# EqualizerTop.net
KiCad netlist of a schematic drawn in Altium Designer
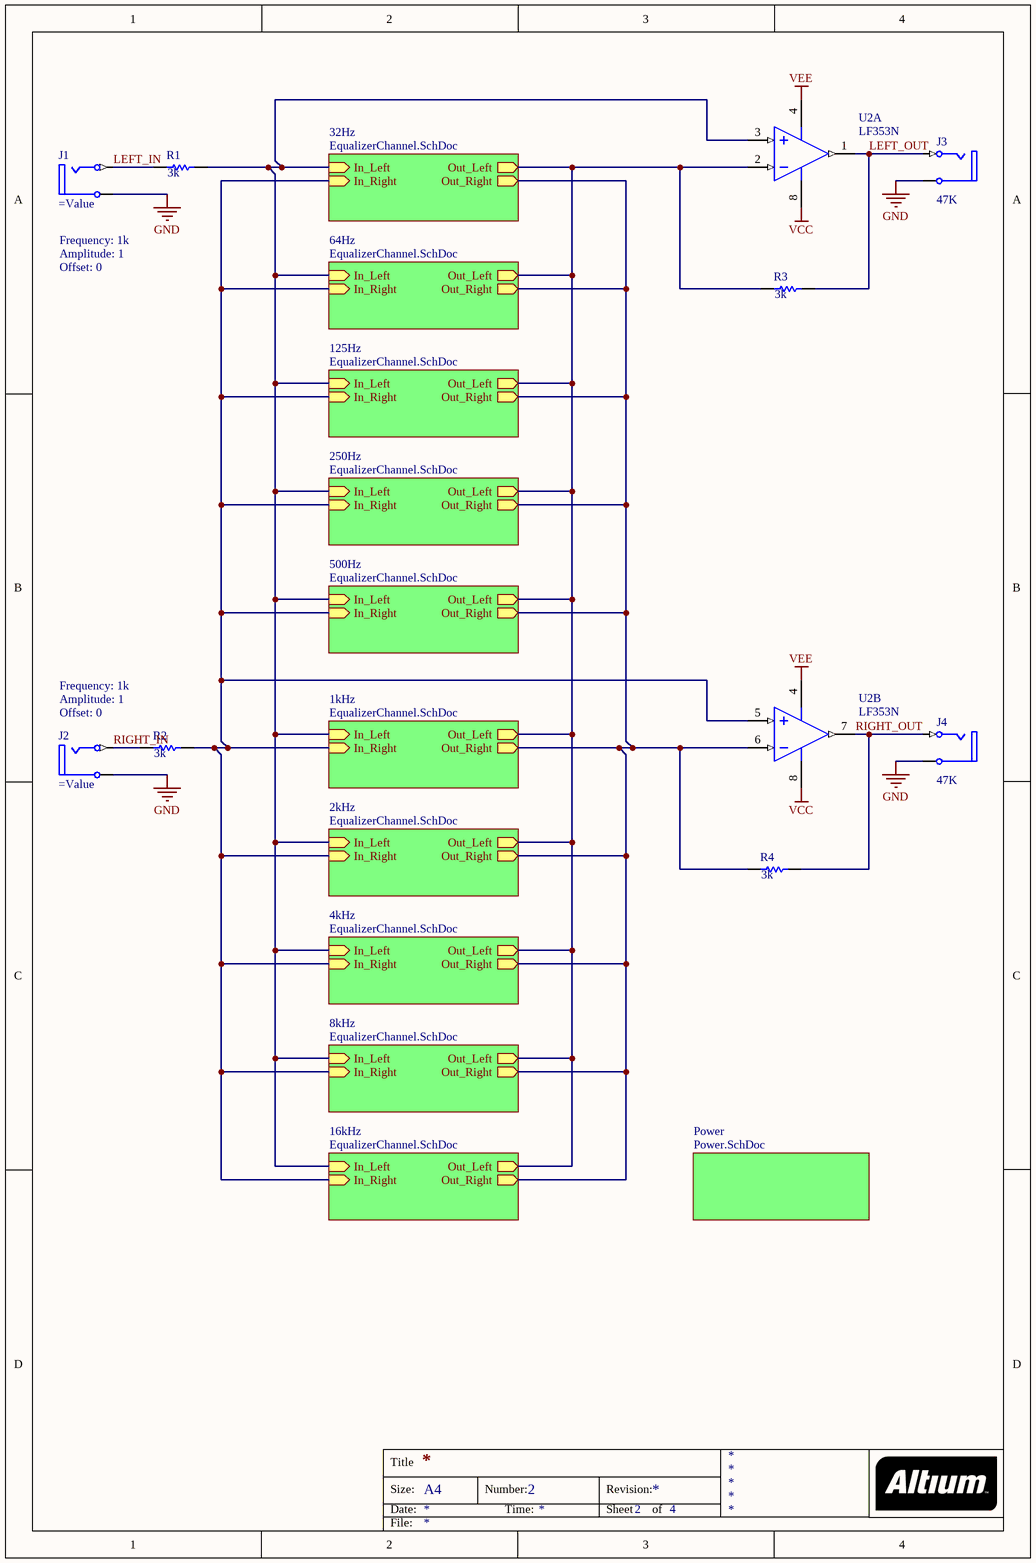
[diagram p0: EqualizerTop.SchDoc]

(export (version "E")
  (design (tool "Eeschema 10.0.6"))
  (components
    (comp (ref "J1")
      (value "~")
      (footprint "AudioEqualizer:RCA/4.5-H2")
      (description "RCA Phono Jack, Right Angle, Thru-Hole, Snap-In")
      (fields
        (field (name "OFFSET") "0")
        (field (name "AMPLITUDE") "1")
        (field (name "FREQUENCY") "1k")
        (field (name "PUBLISHER") "Altium Limited")
      )
      (libsource (lib "Miscellaneous Connectors") (part "RCA"))
    )
    (comp (ref "J2")
      (value "~")
      (footprint "AudioEqualizer:RCA/4.5-H2")
      (description "RCA Phono Jack, Right Angle, Thru-Hole, Snap-In")
      (fields
        (field (name "OFFSET") "0")
        (field (name "AMPLITUDE") "1")
        (field (name "FREQUENCY") "1k")
        (field (name "PUBLISHER") "Altium Limited")
      )
      (libsource (lib "Miscellaneous Connectors") (part "RCA"))
    )
    (comp (ref "J3")
      (value "47K")
      (footprint "AudioEqualizer:RCA/4.5-H2")
      (description "RCA Phono Jack, Right Angle, Thru-Hole, Snap-In")
      (fields (field (name "PUBLISHER") "Altium Limited"))
      (libsource (lib "Miscellaneous Connectors") (part "RCA"))
    )
    (comp (ref "J4")
      (value "47K")
      (footprint "AudioEqualizer:RCA/4.5-H2")
      (description "RCA Phono Jack, Right Angle, Thru-Hole, Snap-In")
      (fields (field (name "PUBLISHER") "Altium Limited"))
      (libsource (lib "Miscellaneous Connectors") (part "RCA"))
    )
    (comp (ref "R1")
      (value "3k")
      (footprint "AudioEqualizer:3216[1206]")
      (description "Resistor")
      (fields (field (name "PUBLISHER") "Altium Limited"))
      (libsource (lib "Miscellaneous Devices") (part "Res1"))
    )
    (comp (ref "R2")
      (value "3k")
      (footprint "AudioEqualizer:3216[1206]")
      (description "Resistor")
      (fields (field (name "PUBLISHER") "Altium Limited"))
      (libsource (lib "Miscellaneous Devices") (part "Res1"))
    )
    (comp (ref "R3")
      (value "3k")
      (footprint "AudioEqualizer:3216[1206]")
      (description "Resistor")
      (fields (field (name "PUBLISHER") "Altium Limited"))
      (libsource (lib "Miscellaneous Devices") (part "Res1"))
    )
    (comp (ref "R4")
      (value "3k")
      (footprint "AudioEqualizer:3216[1206]")
      (description "Resistor")
      (fields (field (name "PUBLISHER") "Altium Limited"))
      (libsource (lib "Miscellaneous Devices") (part "Res1"))
    )
    (comp (ref "U2")
      (value "LF353N")
      (footprint "N08E")
      (description "Wide Bandwidth Dual JFET Input Operational Amplifier, 8-pin MDIP")
      (fields
        (field (name "MANUFACTURER") "National Semiconductor")
        (field (name "PUBLISHER") "Altium Limited")
      )
      (libsource (lib "NSC Amplifier") (part "LF353N"))
    )
  )
  (nets
    (net (code "1") (name "/In_Left") (class "Default")
      (node (ref "R1") (pin "2") (pinfunction "2_2") (pintype "passive"))
      (node (ref "U2") (pin "3") (pinfunction "INA+_3") (pintype "input"))
    )
    (net (code "2") (name "/In_Right") (class "Default")
      (node (ref "R2") (pin "2") (pinfunction "2_2") (pintype "passive"))
      (node (ref "U2") (pin "5") (pinfunction "INB+_5") (pintype "input"))
    )
    (net (code "3") (name "/LEFT_IN") (class "Default")
      (node (ref "J1") (pin "2B") (pinfunction "Signal_2B") (pintype "input"))
      (node (ref "R1") (pin "1") (pinfunction "1_1") (pintype "passive"))
    )
    (net (code "4") (name "/LEFT_OUT") (class "Default")
      (node (ref "J3") (pin "2B") (pinfunction "Signal_2B") (pintype "input"))
      (node (ref "R3") (pin "2") (pinfunction "2_2") (pintype "passive"))
      (node (ref "U2") (pin "1") (pinfunction "OUTA_1") (pintype "output"))
    )
    (net (code "5") (name "/Out_Left") (class "Default")
      (node (ref "R3") (pin "1") (pinfunction "1_1") (pintype "passive"))
      (node (ref "U2") (pin "2") (pinfunction "INA-_2") (pintype "input"))
    )
    (net (code "6") (name "/Out_Right") (class "Default")
      (node (ref "R4") (pin "1") (pinfunction "1_1") (pintype "passive"))
      (node (ref "U2") (pin "6") (pinfunction "INB-_6") (pintype "input"))
    )
    (net (code "7") (name "/RIGHT_IN") (class "Default")
      (node (ref "J2") (pin "2B") (pinfunction "Signal_2B") (pintype "input"))
      (node (ref "R2") (pin "1") (pinfunction "1_1") (pintype "passive"))
    )
    (net (code "8") (name "/RIGHT_OUT") (class "Default")
      (node (ref "J4") (pin "2B") (pinfunction "Signal_2B") (pintype "input"))
      (node (ref "R4") (pin "2") (pinfunction "2_2") (pintype "passive"))
      (node (ref "U2") (pin "7") (pinfunction "OUTB_7") (pintype "output"))
    )
    (net (code "9") (name "GND") (class "Default")
      (node (ref "J1") (pin "1A") (pinfunction "Ground_1A") (pintype "power_in"))
      (node (ref "J2") (pin "1A") (pinfunction "Ground_1A") (pintype "power_in"))
      (node (ref "J3") (pin "1A") (pinfunction "Ground_1A") (pintype "power_in"))
      (node (ref "J4") (pin "1A") (pinfunction "Ground_1A") (pintype "power_in"))
    )
    (net (code "10") (name "VCC") (class "Default")
      (node (ref "U2") (pin "8") (pinfunction "V+_8") (pintype "power_in"))
    )
    (net (code "11") (name "VEE") (class "Default")
      (node (ref "U2") (pin "4") (pinfunction "V-_4") (pintype "power_in"))
    )
  )
)
